# soundReactiveDotStarV1.net
KiCad netlist of a schematic drawn in EAGLE
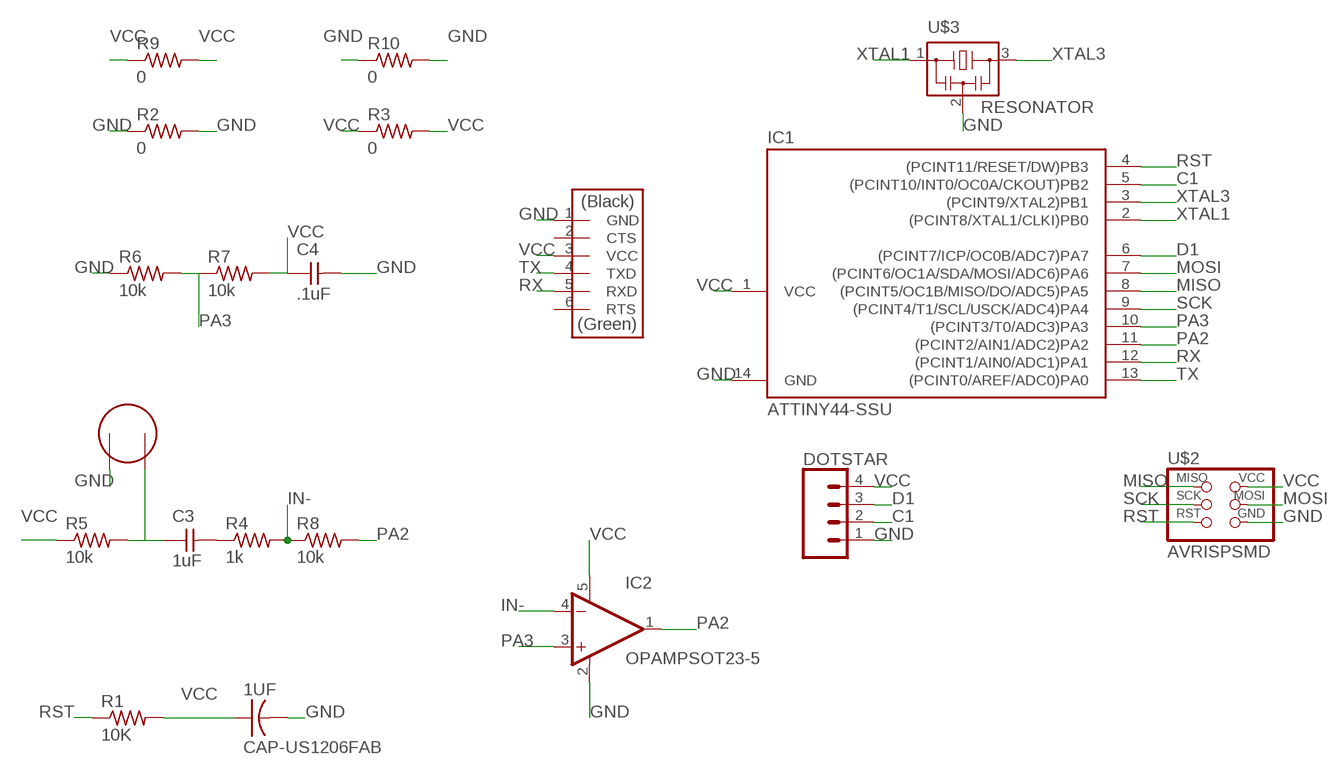
[diagram p0: schematic, sheet 1]

(export (version "E")
  (design (tool "Eeschema 10.0.6"))
  (components
    (comp (ref "1UF")
      (value "CAP-US1206FAB")
      (footprint "eagle-import:C1206FAB")
      (libsource (lib "eagle-import") (part "CAP-US1206FAB"))
    )
    (comp (ref "C3")
      (value "1uF")
      (footprint "eagle-import:C1206FAB")
      (libsource (lib "eagle-import") (part "CAP-UNPOLARIZEDFAB"))
    )
    (comp (ref "C4")
      (value ".1uF")
      (footprint "eagle-import:C1206FAB")
      (libsource (lib "eagle-import") (part "CAP-UNPOLARIZEDFAB"))
    )
    (comp (ref "DOTSTAR")
      (value "CONN_04SMD_RA_FEMALE")
      (footprint "eagle-import:1X04_SMD_RA_FEMALE")
      (libsource (lib "eagle-import") (part "CONN_04SMD_RA_FEMALE"))
    )
    (comp (ref "IC1")
      (value "ATTINY44-SSU")
      (footprint "eagle-import:SOIC14")
      (libsource (lib "eagle-import") (part "ATTINY44-SSU"))
    )
    (comp (ref "IC2")
      (value "OPAMPSOT23-5")
      (footprint "eagle-import:SOT23-5")
      (libsource (lib "eagle-import") (part "OPAMPSOT23-5"))
    )
    (comp (ref "R1")
      (value "10K")
      (footprint "eagle-import:R1206FAB")
      (libsource (lib "eagle-import") (part "RES-US1206FAB"))
    )
    (comp (ref "R2")
      (value "0")
      (footprint "eagle-import:R1206FAB")
      (libsource (lib "eagle-import") (part "RES-US1206FAB"))
    )
    (comp (ref "R3")
      (value "0")
      (footprint "eagle-import:R1206FAB")
      (libsource (lib "eagle-import") (part "RES-US1206FAB"))
    )
    (comp (ref "R4")
      (value "1k")
      (footprint "eagle-import:R1206FAB")
      (libsource (lib "eagle-import") (part "RES-US1206FAB"))
    )
    (comp (ref "R5")
      (value "10k")
      (footprint "eagle-import:R1206FAB")
      (libsource (lib "eagle-import") (part "RES-US1206FAB"))
    )
    (comp (ref "R6")
      (value "10k")
      (footprint "eagle-import:R1206FAB")
      (libsource (lib "eagle-import") (part "RES-US1206FAB"))
    )
    (comp (ref "R7")
      (value "10k")
      (footprint "eagle-import:R1206FAB")
      (libsource (lib "eagle-import") (part "RES-US1206FAB"))
    )
    (comp (ref "R8")
      (value "10k")
      (footprint "eagle-import:R1206FAB")
      (libsource (lib "eagle-import") (part "RES-US1206FAB"))
    )
    (comp (ref "R9")
      (value "0")
      (footprint "eagle-import:R1206FAB")
      (libsource (lib "eagle-import") (part "RES-US1206FAB"))
    )
    (comp (ref "R10")
      (value "0")
      (footprint "eagle-import:R1206FAB")
      (libsource (lib "eagle-import") (part "RES-US1206FAB"))
    )
    (comp (ref "U$1")
      (value "FTDI-SMD-HEADER")
      (footprint "eagle-import:1X06SMD")
      (libsource (lib "eagle-import") (part "FTDI-SMD-HEADER"))
    )
    (comp (ref "U$2")
      (value "AVRISPSMD")
      (footprint "eagle-import:2X03SMD")
      (libsource (lib "eagle-import") (part "AVRISPSMD"))
    )
    (comp (ref "U$3")
      (value "RESONATOR")
      (footprint "eagle-import:EFOBM")
      (libsource (lib "eagle-import") (part "RESONATOR"))
    )
    (comp (ref "U$4")
      (value "ELECTRET")
      (footprint "eagle-import:ELECTRET_2742PBJ-A")
      (libsource (lib "eagle-import") (part "ELECTRET"))
    )
  )
  (nets
    (net (code "1") (name "/C1") (class "Default")
      (node (ref "DOTSTAR") (pin "2") (pinfunction "2_2") (pintype "passive"))
      (node (ref "IC1") (pin "5") (pinfunction "(PCINT10/INT0/OC0A/CKOUT)PB2_5") (pintype "bidirectional"))
    )
    (net (code "2") (name "/D1") (class "Default")
      (node (ref "DOTSTAR") (pin "3") (pinfunction "3_3") (pintype "passive"))
      (node (ref "IC1") (pin "6") (pinfunction "(PCINT7/ICP/OC0B/ADC7)PA7_6") (pintype "bidirectional"))
    )
    (net (code "3") (name "/GND") (class "Default")
      (node (ref "1UF") (pin "2") (pinfunction "2_2") (pintype "passive"))
      (node (ref "C4") (pin "2") (pinfunction "2_2") (pintype "passive"))
      (node (ref "DOTSTAR") (pin "1") (pinfunction "1_1") (pintype "passive"))
      (node (ref "IC1") (pin "14") (pinfunction "GND_14") (pintype "power_in"))
      (node (ref "IC2") (pin "2") (pinfunction "V-_2") (pintype "power_in"))
      (node (ref "R10") (pin "1") (pinfunction "1_1") (pintype "passive"))
      (node (ref "R10") (pin "2") (pinfunction "2_2") (pintype "passive"))
      (node (ref "R2") (pin "1") (pinfunction "1_1") (pintype "passive"))
      (node (ref "R2") (pin "2") (pinfunction "2_2") (pintype "passive"))
      (node (ref "R6") (pin "1") (pinfunction "1_1") (pintype "passive"))
      (node (ref "U$1") (pin "1") (pinfunction "GND_1") (pintype "bidirectional"))
      (node (ref "U$2") (pin "6") (pinfunction "GND_6") (pintype "passive"))
      (node (ref "U$3") (pin "2") (pinfunction "2_2") (pintype "passive"))
      (node (ref "U$4") (pin "P$1") (pinfunction "P$1_P$1") (pintype "bidirectional"))
    )
    (net (code "4") (name "/IN-") (class "Default")
      (node (ref "IC2") (pin "4") (pinfunction "-IN_4") (pintype "input"))
      (node (ref "R4") (pin "2") (pinfunction "2_2") (pintype "passive"))
      (node (ref "R8") (pin "1") (pinfunction "1_1") (pintype "passive"))
    )
    (net (code "5") (name "/MISO") (class "Default")
      (node (ref "IC1") (pin "8") (pinfunction "(PCINT5/OC1B/MISO/DO/ADC5)PA5_8") (pintype "bidirectional"))
      (node (ref "U$2") (pin "1") (pinfunction "MISO_1") (pintype "passive"))
    )
    (net (code "6") (name "/MOSI") (class "Default")
      (node (ref "IC1") (pin "7") (pinfunction "(PCINT6/OC1A/SDA/MOSI/ADC6)PA6_7") (pintype "bidirectional"))
      (node (ref "U$2") (pin "4") (pinfunction "MOSI_4") (pintype "passive"))
    )
    (net (code "7") (name "/PA2") (class "Default")
      (node (ref "IC1") (pin "11") (pinfunction "(PCINT2/AIN1/ADC2)PA2_11") (pintype "bidirectional"))
      (node (ref "IC2") (pin "1") (pinfunction "OUT_1") (pintype "output"))
      (node (ref "R8") (pin "2") (pinfunction "2_2") (pintype "passive"))
    )
    (net (code "8") (name "/PA3") (class "Default")
      (node (ref "IC1") (pin "10") (pinfunction "(PCINT3/T0/ADC3)PA3_10") (pintype "bidirectional"))
      (node (ref "IC2") (pin "3") (pinfunction "+IN_3") (pintype "input"))
      (node (ref "R6") (pin "2") (pinfunction "2_2") (pintype "passive"))
      (node (ref "R7") (pin "1") (pinfunction "1_1") (pintype "passive"))
    )
    (net (code "9") (name "/RST") (class "Default")
      (node (ref "IC1") (pin "4") (pinfunction "(PCINT11/RESET/DW)PB3_4") (pintype "bidirectional"))
      (node (ref "R1") (pin "1") (pinfunction "1_1") (pintype "passive"))
      (node (ref "U$2") (pin "5") (pinfunction "RST_5") (pintype "passive"))
    )
    (net (code "10") (name "/RX") (class "Default")
      (node (ref "IC1") (pin "12") (pinfunction "(PCINT1/AIN0/ADC1)PA1_12") (pintype "bidirectional"))
      (node (ref "U$1") (pin "5") (pinfunction "RXD_5") (pintype "bidirectional"))
    )
    (net (code "11") (name "/SCK") (class "Default")
      (node (ref "IC1") (pin "9") (pinfunction "(PCINT4/T1/SCL/USCK/ADC4)PA4_9") (pintype "bidirectional"))
      (node (ref "U$2") (pin "3") (pinfunction "SCK_3") (pintype "passive"))
    )
    (net (code "12") (name "/TX") (class "Default")
      (node (ref "IC1") (pin "13") (pinfunction "(PCINT0/AREF/ADC0)PA0_13") (pintype "bidirectional"))
      (node (ref "U$1") (pin "4") (pinfunction "TXD_4") (pintype "bidirectional"))
    )
    (net (code "13") (name "/VCC") (class "Default")
      (node (ref "1UF") (pin "1") (pinfunction "1_1") (pintype "passive"))
      (node (ref "C4") (pin "1") (pinfunction "1_1") (pintype "passive"))
      (node (ref "DOTSTAR") (pin "4") (pinfunction "4_4") (pintype "passive"))
      (node (ref "IC1") (pin "1") (pinfunction "VCC_1") (pintype "power_in"))
      (node (ref "IC2") (pin "5") (pinfunction "V+_5") (pintype "power_in"))
      (node (ref "R1") (pin "2") (pinfunction "2_2") (pintype "passive"))
      (node (ref "R3") (pin "1") (pinfunction "1_1") (pintype "passive"))
      (node (ref "R3") (pin "2") (pinfunction "2_2") (pintype "passive"))
      (node (ref "R5") (pin "1") (pinfunction "1_1") (pintype "passive"))
      (node (ref "R7") (pin "2") (pinfunction "2_2") (pintype "passive"))
      (node (ref "R9") (pin "1") (pinfunction "1_1") (pintype "passive"))
      (node (ref "R9") (pin "2") (pinfunction "2_2") (pintype "passive"))
      (node (ref "U$1") (pin "3") (pinfunction "VCC_3") (pintype "bidirectional"))
      (node (ref "U$2") (pin "2") (pinfunction "VCC_2") (pintype "passive"))
    )
    (net (code "14") (name "/XTAL1") (class "Default")
      (node (ref "IC1") (pin "2") (pinfunction "(PCINT8/XTAL1/CLKI)PB0_2") (pintype "bidirectional"))
      (node (ref "U$3") (pin "1") (pinfunction "1_1") (pintype "passive"))
    )
    (net (code "15") (name "/XTAL3") (class "Default")
      (node (ref "IC1") (pin "3") (pinfunction "(PCINT9/XTAL2)PB1_3") (pintype "bidirectional"))
      (node (ref "U$3") (pin "3") (pinfunction "3_3") (pintype "passive"))
    )
    (net (code "16") (name "Net-(C3-Pad1)") (class "Default")
      (node (ref "C3") (pin "1") (pinfunction "1_1") (pintype "passive"))
      (node (ref "R5") (pin "2") (pinfunction "2_2") (pintype "passive"))
      (node (ref "U$4") (pin "P$2") (pinfunction "P$2_P$2") (pintype "bidirectional"))
    )
    (net (code "17") (name "Net-(C3-Pad2)") (class "Default")
      (node (ref "C3") (pin "2") (pinfunction "2_2") (pintype "passive"))
      (node (ref "R4") (pin "1") (pinfunction "1_1") (pintype "passive"))
    )
    (net (code "18") (name "unconnected-(U$1-CTS-Pad2)") (class "Default")
      (node (ref "U$1") (pin "2") (pinfunction "CTS_2") (pintype "bidirectional"))
    )
    (net (code "19") (name "unconnected-(U$1-RTS-Pad6)") (class "Default")
      (node (ref "U$1") (pin "6") (pinfunction "RTS_6") (pintype "bidirectional"))
    )
  )
)
